# Sheet1.net
KiCad netlist of a schematic drawn in Altium Designer
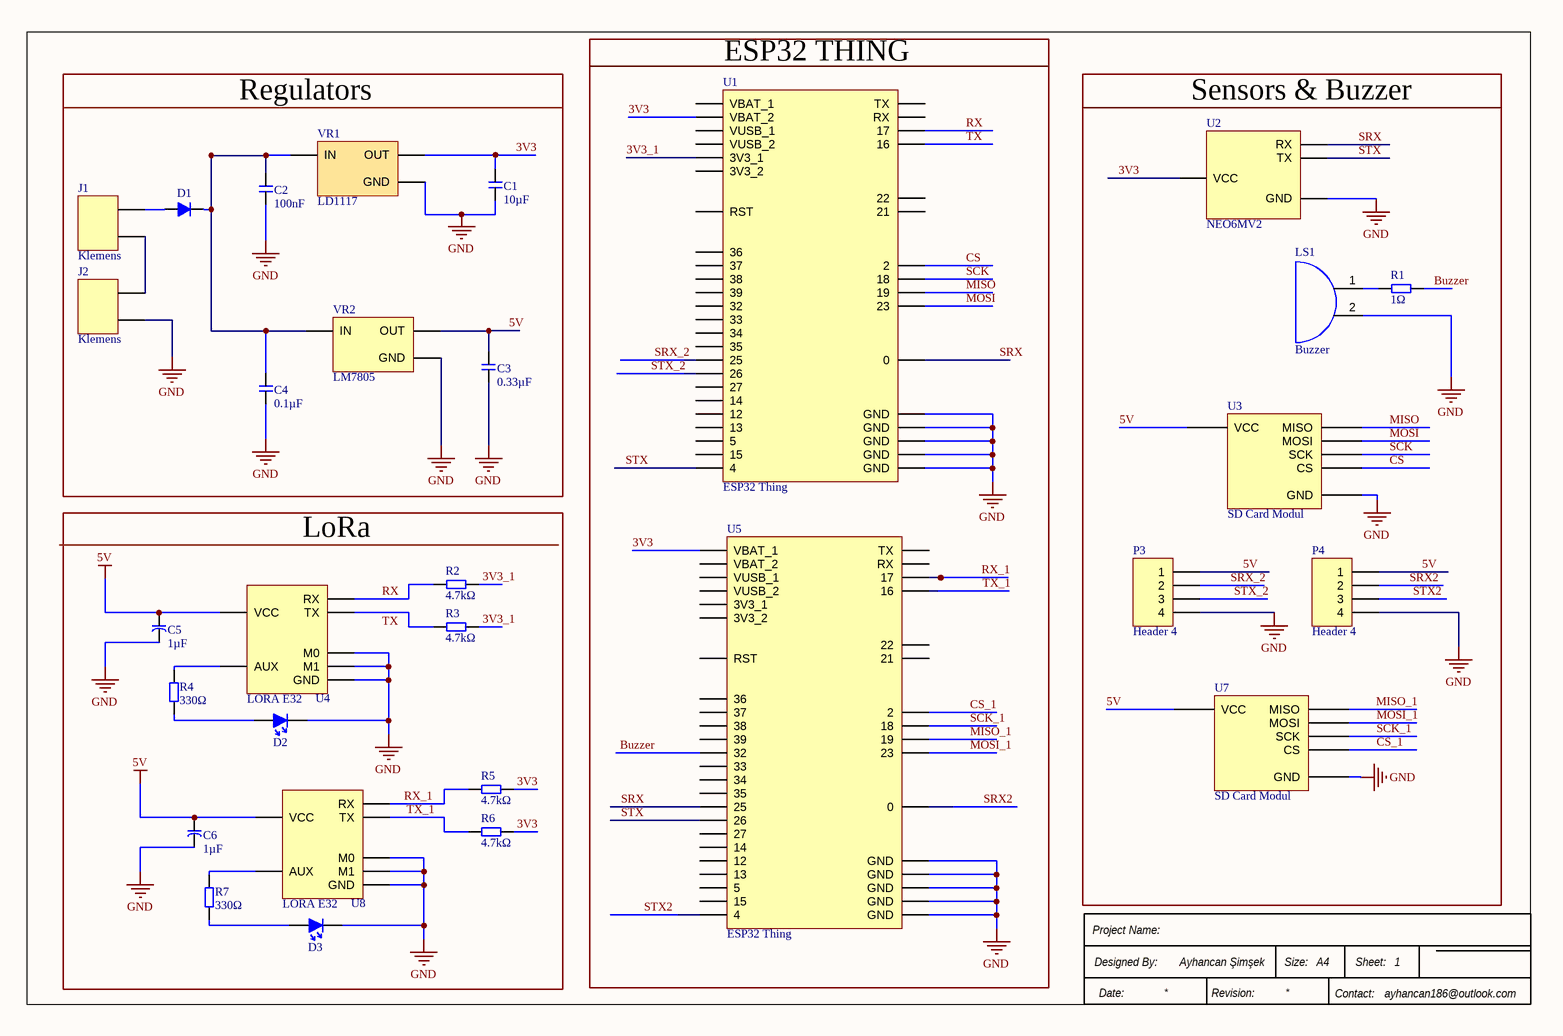
[diagram p0: Sheet1.SchDoc]

(export (version "E")
  (design (tool "Eeschema 10.0.6"))
  (components
    (comp (ref "C1") (value "10µF") (footprint "LCapacitor") (libsource (lib "Schlib1") (part "Capacitor")))
    (comp (ref "C2") (value "100nF") (footprint "LCapacitor") (libsource (lib "Schlib1") (part "Capacitor")))
    (comp (ref "C3") (value "0.33µF") (footprint "LCapacitor") (libsource (lib "Schlib1") (part "Capacitor")))
    (comp (ref "C4") (value "0.1µF") (footprint "LCapacitor") (libsource (lib "Schlib1") (part "Capacitor")))
    (comp (ref "C5") (value "1µF") (footprint "Capacitor") (libsource (lib "Schlib1") (part "DCapacitor")))
    (comp (ref "C6") (value "1µF") (footprint "Capacitor") (libsource (lib "Schlib1") (part "DCapacitor")))
    (comp (ref "D1")
      (value "Diode")
      (footprint "Zener")
      (libsource (lib "Integrated_Library2") (part "Diode"))
    )
    (comp (ref "D2") (value "Led") (footprint "LED") (libsource (lib "Integrated_Library2") (part "Led")))
    (comp (ref "D3") (value "Led") (footprint "LED") (libsource (lib "Integrated_Library2") (part "Led")))
    (comp (ref "J1")
      (value "Klemens")
      (footprint "Klemens")
      (libsource (lib "Integrated_Library2") (part "Klemens"))
    )
    (comp (ref "J2")
      (value "Klemens")
      (footprint "Klemens")
      (libsource (lib "Integrated_Library2") (part "Klemens"))
    )
    (comp (ref "LS1")
      (value "Buzzer")
      (footprint "Buzzer")
      (libsource (lib "Integrated_Library2") (part "Buzzer"))
    )
    (comp (ref "P3")
      (value "Header 4")
      (footprint "HDR1X4")
      (description "Header, 4-Pin")
      (fields (field (name "PUBLISHER") "Altium Limited"))
      (libsource (lib "Miscellaneous Connectors") (part "Header 4"))
    )
    (comp (ref "P4")
      (value "Header 4")
      (footprint "HDR1X4")
      (description "Header, 4-Pin")
      (fields (field (name "PUBLISHER") "Altium Limited"))
      (libsource (lib "Miscellaneous Connectors") (part "Header 4"))
    )
    (comp (ref "R1") (value "1Ω") (footprint "Resistor") (libsource (lib "Schlib1") (part "Resistor")))
    (comp (ref "R2") (value "4.7kΩ") (footprint "Resistor") (libsource (lib "Schlib1") (part "Resistor")))
    (comp (ref "R3") (value "4.7kΩ") (footprint "Resistor") (libsource (lib "Schlib1") (part "Resistor")))
    (comp (ref "R4") (value "330Ω") (footprint "Resistor") (libsource (lib "Schlib1") (part "Resistor")))
    (comp (ref "R5") (value "4.7kΩ") (footprint "Resistor") (libsource (lib "Schlib1") (part "Resistor")))
    (comp (ref "R6") (value "4.7kΩ") (footprint "Resistor") (libsource (lib "Schlib1") (part "Resistor")))
    (comp (ref "R7") (value "330Ω") (footprint "Resistor") (libsource (lib "Schlib1") (part "Resistor")))
    (comp (ref "U1")
      (value "ESP32 Thing")
      (footprint "ESP32 THING")
      (description "ESP32 802.11 Wireless LAN/Combo Wireless Module Development Kit")
      (fields (field (name "MANUFACTURER") "SparkFun") (field (name "MANUFACTURER PART NUMBER") "DEV-13907"))
      (libsource (lib "Integrated_Library2") (part "ESP32 Thing"))
    )
    (comp (ref "U2")
      (value "NEO6MV2")
      (footprint "NEO6MV2")
      (description "U#NEO-6M Gps Module U-BLOX6 SMD24P")
      (fields (field (name "MANUFACTURER") "u-blox") (field (name "MANUFACTURER PART NUMBER") "NEO-6M-0"))
      (libsource (lib "Integrated_Library2") (part "NEO6MV2"))
    )
    (comp (ref "U3")
      (value "SD Card Modul")
      (footprint "SD Card Modülü")
      (libsource (lib "Integrated_Library2") (part "SD Card Modul"))
    )
    (comp (ref "U4")
      (value "LORA E32")
      (footprint "LORAE32")
      (description "WiFi-Modul 802.11/BT 2, 4-2, 5GHz 150Mb/s")
      (fields
        (field (name "MANUFACTURER") "Espressif Systems")
        (field (name "MANUFACTURER PART NUMBER") "ESP32-S3-WROOM-1-N16R8")
      )
      (libsource (lib "Integrated_Library2") (part "LORA E32"))
    )
    (comp (ref "U5")
      (value "ESP32 Thing")
      (footprint "ESP32 THING")
      (description "ESP32 802.11 Wireless LAN/Combo Wireless Module Development Kit")
      (fields (field (name "MANUFACTURER") "SparkFun") (field (name "MANUFACTURER PART NUMBER") "DEV-13907"))
      (libsource (lib "Integrated_Library2") (part "ESP32 Thing"))
    )
    (comp (ref "U7")
      (value "SD Card Modul")
      (footprint "SD Card Modülü")
      (libsource (lib "Integrated_Library2") (part "SD Card Modul"))
    )
    (comp (ref "U8")
      (value "LORA E32")
      (footprint "LORAE32")
      (description "WiFi-Modul 802.11/BT 2, 4-2, 5GHz 150Mb/s")
      (fields
        (field (name "MANUFACTURER") "Espressif Systems")
        (field (name "MANUFACTURER PART NUMBER") "ESP32-S3-WROOM-1-N16R8")
      )
      (libsource (lib "Integrated_Library2") (part "LORA E32"))
    )
    (comp (ref "VR1")
      (value "LD1117")
      (footprint "LD1117")
      (description "LDO Regulator Pos 3.3V 1.3A 3-Pin(3+Tab) TO-220 Tube (Alt: LD1117V33C)")
      (fields
        (field (name "MANUFACTURER") "STMicroelectronics")
        (field (name "MANUFACTURER PART NUMBER") "LD1117V33C")
      )
      (libsource (lib "Integrated_Library2") (part "LD1117"))
    )
    (comp (ref "VR2")
      (value "LM7805")
      (footprint "LM7805")
      (description "LM78XX Series 5 V Fixed Output 1 A 3-Terminal LDO Voltage Regulator - TO-220")
      (fields
        (field (name "MANUFACTURER") "ON Semiconductor / Fairchild")
        (field (name "MANUFACTURER PART NUMBER") "LM7805CT")
      )
      (libsource (lib "Integrated_Library2") (part "LM7805"))
    )
  )
  (nets
    (net (code "1") (name "/3V3") (class "Default")
      (node (ref "C1") (pin "2") (pinfunction "2_2") (pintype "passive"))
      (node (ref "R5") (pin "2") (pinfunction "2_2") (pintype "passive"))
      (node (ref "R6") (pin "2") (pinfunction "2_2") (pintype "passive"))
      (node (ref "U1") (pin "VBAT_2") (pinfunction "VBAT_2_VBAT_2") (pintype "passive"))
      (node (ref "U2") (pin "1") (pinfunction "VCC_1") (pintype "passive"))
      (node (ref "U5") (pin "VBAT_1") (pinfunction "VBAT_1_VBAT_1") (pintype "passive"))
      (node (ref "VR1") (pin "2") (pinfunction "OUT_2") (pintype "passive"))
    )
    (net (code "2") (name "/3V3_1") (class "Default")
      (node (ref "R2") (pin "2") (pinfunction "2_2") (pintype "passive"))
      (node (ref "R3") (pin "2") (pinfunction "2_2") (pintype "passive"))
      (node (ref "U1") (pin "3V3_1") (pinfunction "3V3_1_3V3_1") (pintype "passive"))
    )
    (net (code "3") (name "/Buzzer") (class "Default")
      (node (ref "R1") (pin "1") (pinfunction "1_1") (pintype "passive"))
      (node (ref "U5") (pin "32") (pinfunction "32_32") (pintype "passive"))
    )
    (net (code "4") (name "/CS") (class "Default")
      (node (ref "U1") (pin "2") (pinfunction "2_2") (pintype "passive"))
      (node (ref "U3") (pin "4") (pinfunction "CS_4") (pintype "passive"))
    )
    (net (code "5") (name "/CS_1") (class "Default")
      (node (ref "U5") (pin "2") (pinfunction "2_2") (pintype "passive"))
      (node (ref "U7") (pin "4") (pinfunction "CS_4") (pintype "passive"))
    )
    (net (code "6") (name "/MISO") (class "Default")
      (node (ref "U1") (pin "19") (pinfunction "19_19") (pintype "passive"))
      (node (ref "U3") (pin "3") (pinfunction "MISO_3") (pintype "passive"))
    )
    (net (code "7") (name "/MISO_1") (class "Default")
      (node (ref "U5") (pin "19") (pinfunction "19_19") (pintype "passive"))
      (node (ref "U7") (pin "3") (pinfunction "MISO_3") (pintype "passive"))
    )
    (net (code "8") (name "/MOSI") (class "Default")
      (node (ref "U1") (pin "23") (pinfunction "23_23") (pintype "passive"))
      (node (ref "U3") (pin "2") (pinfunction "MOSI_2") (pintype "passive"))
    )
    (net (code "9") (name "/MOSI_1") (class "Default")
      (node (ref "U5") (pin "23") (pinfunction "23_23") (pintype "passive"))
      (node (ref "U7") (pin "2") (pinfunction "MOSI_2") (pintype "passive"))
    )
    (net (code "10") (name "/RX") (class "Default")
      (node (ref "R2") (pin "1") (pinfunction "1_1") (pintype "passive"))
      (node (ref "U1") (pin "17") (pinfunction "17_17") (pintype "passive"))
      (node (ref "U4") (pin "5") (pinfunction "RX_5") (pintype "passive"))
    )
    (net (code "11") (name "/RX_1") (class "Default")
      (node (ref "R5") (pin "1") (pinfunction "1_1") (pintype "passive"))
      (node (ref "U5") (pin "17") (pinfunction "17_17") (pintype "passive"))
      (node (ref "U8") (pin "5") (pinfunction "RX_5") (pintype "passive"))
    )
    (net (code "12") (name "/SCK") (class "Default")
      (node (ref "U1") (pin "18") (pinfunction "18_18") (pintype "passive"))
      (node (ref "U3") (pin "1") (pinfunction "SCK_1") (pintype "passive"))
    )
    (net (code "13") (name "/SCK_1") (class "Default")
      (node (ref "U5") (pin "18") (pinfunction "18_18") (pintype "passive"))
      (node (ref "U7") (pin "1") (pinfunction "SCK_1") (pintype "passive"))
    )
    (net (code "14") (name "/SRX") (class "Default")
      (node (ref "U1") (pin "0") (pinfunction "0_0") (pintype "passive"))
      (node (ref "U2") (pin "2") (pinfunction "RX_2") (pintype "passive"))
      (node (ref "U5") (pin "25") (pinfunction "25_25") (pintype "passive"))
    )
    (net (code "15") (name "/SRX2") (class "Default")
      (node (ref "P4") (pin "2") (pinfunction "2_2") (pintype "passive"))
      (node (ref "U5") (pin "0") (pinfunction "0_0") (pintype "passive"))
    )
    (net (code "16") (name "/SRX_2") (class "Default")
      (node (ref "P3") (pin "2") (pinfunction "2_2") (pintype "passive"))
      (node (ref "U1") (pin "25") (pinfunction "25_25") (pintype "passive"))
    )
    (net (code "17") (name "/STX") (class "Default")
      (node (ref "U1") (pin "4") (pinfunction "4_4") (pintype "passive"))
      (node (ref "U2") (pin "3") (pinfunction "TX_3") (pintype "passive"))
      (node (ref "U5") (pin "26") (pinfunction "26_26") (pintype "passive"))
    )
    (net (code "18") (name "/STX2") (class "Default")
      (node (ref "P4") (pin "3") (pinfunction "3_3") (pintype "passive"))
      (node (ref "U5") (pin "4") (pinfunction "4_4") (pintype "passive"))
    )
    (net (code "19") (name "/STX_2") (class "Default")
      (node (ref "P3") (pin "3") (pinfunction "3_3") (pintype "passive"))
      (node (ref "U1") (pin "26") (pinfunction "26_26") (pintype "passive"))
    )
    (net (code "20") (name "/TX") (class "Default")
      (node (ref "R3") (pin "1") (pinfunction "1_1") (pintype "passive"))
      (node (ref "U1") (pin "16") (pinfunction "16_16") (pintype "passive"))
      (node (ref "U4") (pin "4") (pinfunction "TX_4") (pintype "passive"))
    )
    (net (code "21") (name "/TX_1") (class "Default")
      (node (ref "R6") (pin "1") (pinfunction "1_1") (pintype "passive"))
      (node (ref "U5") (pin "16") (pinfunction "16_16") (pintype "passive"))
      (node (ref "U8") (pin "4") (pinfunction "TX_4") (pintype "passive"))
    )
    (net (code "22") (name "5V") (class "Default")
      (node (ref "C3") (pin "2") (pinfunction "2_2") (pintype "passive"))
      (node (ref "C5") (pin "1") (pinfunction "1_1") (pintype "passive"))
      (node (ref "C6") (pin "1") (pinfunction "1_1") (pintype "passive"))
      (node (ref "P3") (pin "1") (pinfunction "1_1") (pintype "passive"))
      (node (ref "P4") (pin "1") (pinfunction "1_1") (pintype "passive"))
      (node (ref "U3") (pin "0") (pinfunction "VCC_0") (pintype "passive"))
      (node (ref "U4") (pin "2") (pinfunction "VCC_2") (pintype "passive"))
      (node (ref "U7") (pin "0") (pinfunction "VCC_0") (pintype "passive"))
      (node (ref "U8") (pin "2") (pinfunction "VCC_2") (pintype "passive"))
      (node (ref "VR2") (pin "3") (pinfunction "OUT_3") (pintype "passive"))
    )
    (net (code "23") (name "GND") (class "Default")
      (node (ref "C1") (pin "1") (pinfunction "1_1") (pintype "passive"))
      (node (ref "C2") (pin "1") (pinfunction "1_1") (pintype "passive"))
      (node (ref "C3") (pin "1") (pinfunction "1_1") (pintype "passive"))
      (node (ref "C4") (pin "1") (pinfunction "1_1") (pintype "passive"))
      (node (ref "C5") (pin "2") (pinfunction "2_2") (pintype "passive"))
      (node (ref "C6") (pin "2") (pinfunction "2_2") (pintype "passive"))
      (node (ref "D2") (pin "1") (pinfunction "1_1") (pintype "power_in"))
      (node (ref "D3") (pin "1") (pinfunction "1_1") (pintype "power_in"))
      (node (ref "J2") (pin "1") (pinfunction "1_1") (pintype "passive"))
      (node (ref "LS1") (pin "2") (pinfunction "2_2") (pintype "passive"))
      (node (ref "P3") (pin "4") (pinfunction "4_4") (pintype "passive"))
      (node (ref "P4") (pin "4") (pinfunction "4_4") (pintype "passive"))
      (node (ref "U1") (pin "GND_1") (pinfunction "GND_GND_1") (pintype "passive"))
      (node (ref "U1") (pin "GND_2") (pinfunction "GND_GND_2") (pintype "passive"))
      (node (ref "U1") (pin "GND_3") (pinfunction "GND_GND_3") (pintype "passive"))
      (node (ref "U1") (pin "GND_4") (pinfunction "GND_GND_4") (pintype "passive"))
      (node (ref "U1") (pin "GND_5") (pinfunction "GND_GND_5") (pintype "passive"))
      (node (ref "U2") (pin "4") (pinfunction "GND_4") (pintype "passive"))
      (node (ref "U3") (pin "5") (pinfunction "GND_5") (pintype "passive"))
      (node (ref "U4") (pin "1") (pinfunction "GND_1") (pintype "passive"))
      (node (ref "U4") (pin "6") (pinfunction "M1_6") (pintype "passive"))
      (node (ref "U4") (pin "7") (pinfunction "M0_7") (pintype "passive"))
      (node (ref "U5") (pin "GND_1") (pinfunction "GND_GND_1") (pintype "passive"))
      (node (ref "U5") (pin "GND_2") (pinfunction "GND_GND_2") (pintype "passive"))
      (node (ref "U5") (pin "GND_3") (pinfunction "GND_GND_3") (pintype "passive"))
      (node (ref "U5") (pin "GND_4") (pinfunction "GND_GND_4") (pintype "passive"))
      (node (ref "U5") (pin "GND_5") (pinfunction "GND_GND_5") (pintype "passive"))
      (node (ref "U7") (pin "5") (pinfunction "GND_5") (pintype "passive"))
      (node (ref "U8") (pin "1") (pinfunction "GND_1") (pintype "passive"))
      (node (ref "U8") (pin "6") (pinfunction "M1_6") (pintype "passive"))
      (node (ref "U8") (pin "7") (pinfunction "M0_7") (pintype "passive"))
      (node (ref "VR1") (pin "3") (pinfunction "GND_3") (pintype "passive"))
      (node (ref "VR2") (pin "2") (pinfunction "GND_2") (pintype "passive"))
    )
    (net (code "24") (name "Net-(D1-Pad1)") (class "Default")
      (node (ref "D1") (pin "1") (pinfunction "1_1") (pintype "passive"))
      (node (ref "J1") (pin "0") (pinfunction "0_0") (pintype "passive"))
    )
    (net (code "25") (name "Net-(D2-Pad2)") (class "Default")
      (node (ref "D2") (pin "2") (pinfunction "2_2") (pintype "power_in"))
      (node (ref "R4") (pin "1") (pinfunction "1_1") (pintype "passive"))
    )
    (net (code "26") (name "Net-(D3-Pad2)") (class "Default")
      (node (ref "D3") (pin "2") (pinfunction "2_2") (pintype "power_in"))
      (node (ref "R7") (pin "1") (pinfunction "1_1") (pintype "passive"))
    )
    (net (code "27") (name "Net-(J1-Pad1)") (class "Default")
      (node (ref "J1") (pin "1") (pinfunction "1_1") (pintype "passive"))
      (node (ref "J2") (pin "0") (pinfunction "0_0") (pintype "passive"))
    )
    (net (code "28") (name "Net-(LS1-Pad1)") (class "Default")
      (node (ref "LS1") (pin "1") (pinfunction "1_1") (pintype "passive"))
      (node (ref "R1") (pin "2") (pinfunction "2_2") (pintype "passive"))
    )
    (net (code "29") (name "Net-(U4-AUX)") (class "Default")
      (node (ref "R4") (pin "2") (pinfunction "2_2") (pintype "passive"))
      (node (ref "U4") (pin "3") (pinfunction "AUX_3") (pintype "passive"))
    )
    (net (code "30") (name "Net-(U8-AUX)") (class "Default")
      (node (ref "R7") (pin "2") (pinfunction "2_2") (pintype "passive"))
      (node (ref "U8") (pin "3") (pinfunction "AUX_3") (pintype "passive"))
    )
    (net (code "31") (name "Net-(VR1-IN)") (class "Default")
      (node (ref "C2") (pin "2") (pinfunction "2_2") (pintype "passive"))
      (node (ref "C4") (pin "2") (pinfunction "2_2") (pintype "passive"))
      (node (ref "D1") (pin "2") (pinfunction "2_2") (pintype "passive"))
      (node (ref "VR1") (pin "1") (pinfunction "IN_1") (pintype "passive"))
      (node (ref "VR2") (pin "1") (pinfunction "IN_1") (pintype "passive"))
    )
    (net (code "32") (name "unconnected-(U1-Pad3V3_2)") (class "Default")
      (node (ref "U1") (pin "3V3_2") (pinfunction "3V3_2_3V3_2") (pintype "passive"))
    )
    (net (code "33") (name "unconnected-(U1-Pad5)") (class "Default")
      (node (ref "U1") (pin "5") (pinfunction "5_5") (pintype "passive"))
    )
    (net (code "34") (name "unconnected-(U1-Pad12)") (class "Default")
      (node (ref "U1") (pin "12") (pinfunction "12_12") (pintype "passive"))
    )
    (net (code "35") (name "unconnected-(U1-Pad13)") (class "Default")
      (node (ref "U1") (pin "13") (pinfunction "13_13") (pintype "passive"))
    )
    (net (code "36") (name "unconnected-(U1-Pad14)") (class "Default")
      (node (ref "U1") (pin "14") (pinfunction "14_14") (pintype "passive"))
    )
    (net (code "37") (name "unconnected-(U1-Pad15)") (class "Default")
      (node (ref "U1") (pin "15") (pinfunction "15_15") (pintype "passive"))
    )
    (net (code "38") (name "unconnected-(U1-Pad21)") (class "Default")
      (node (ref "U1") (pin "21") (pinfunction "21_21") (pintype "passive"))
    )
    (net (code "39") (name "unconnected-(U1-Pad22)") (class "Default")
      (node (ref "U1") (pin "22") (pinfunction "22_22") (pintype "passive"))
    )
    (net (code "40") (name "unconnected-(U1-Pad27)") (class "Default")
      (node (ref "U1") (pin "27") (pinfunction "27_27") (pintype "passive"))
    )
    (net (code "41") (name "unconnected-(U1-Pad32)") (class "Default")
      (node (ref "U1") (pin "32") (pinfunction "32_32") (pintype "passive"))
    )
    (net (code "42") (name "unconnected-(U1-Pad33)") (class "Default")
      (node (ref "U1") (pin "33") (pinfunction "33_33") (pintype "passive"))
    )
    (net (code "43") (name "unconnected-(U1-Pad34)") (class "Default")
      (node (ref "U1") (pin "34") (pinfunction "34_34") (pintype "passive"))
    )
    (net (code "44") (name "unconnected-(U1-Pad35)") (class "Default")
      (node (ref "U1") (pin "35") (pinfunction "35_35") (pintype "passive"))
    )
    (net (code "45") (name "unconnected-(U1-Pad36)") (class "Default")
      (node (ref "U1") (pin "36") (pinfunction "36_36") (pintype "passive"))
    )
    (net (code "46") (name "unconnected-(U1-Pad37)") (class "Default")
      (node (ref "U1") (pin "37") (pinfunction "37_37") (pintype "passive"))
    )
    (net (code "47") (name "unconnected-(U1-Pad38)") (class "Default")
      (node (ref "U1") (pin "38") (pinfunction "38_38") (pintype "passive"))
    )
    (net (code "48") (name "unconnected-(U1-Pad39)") (class "Default")
      (node (ref "U1") (pin "39") (pinfunction "39_39") (pintype "passive"))
    )
    (net (code "49") (name "unconnected-(U1-PadRST)") (class "Default")
      (node (ref "U1") (pin "RST") (pinfunction "RST_RST") (pintype "passive"))
    )
    (net (code "50") (name "unconnected-(U1-PadRX)") (class "Default")
      (node (ref "U1") (pin "RX") (pinfunction "RX_RX") (pintype "passive"))
    )
    (net (code "51") (name "unconnected-(U1-PadTX)") (class "Default")
      (node (ref "U1") (pin "TX") (pinfunction "TX_TX") (pintype "passive"))
    )
    (net (code "52") (name "unconnected-(U1-PadVBAT_1)") (class "Default")
      (node (ref "U1") (pin "VBAT_1") (pinfunction "VBAT_1_VBAT_1") (pintype "passive"))
    )
    (net (code "53") (name "unconnected-(U1-PadVUSB_1)") (class "Default")
      (node (ref "U1") (pin "VUSB_1") (pinfunction "VUSB_1_VUSB_1") (pintype "passive"))
    )
    (net (code "54") (name "unconnected-(U1-PadVUSB_2)") (class "Default")
      (node (ref "U1") (pin "VUSB_2") (pinfunction "VUSB_2_VUSB_2") (pintype "passive"))
    )
    (net (code "55") (name "unconnected-(U5-Pad3V3_1)") (class "Default")
      (node (ref "U5") (pin "3V3_1") (pinfunction "3V3_1_3V3_1") (pintype "passive"))
    )
    (net (code "56") (name "unconnected-(U5-Pad3V3_2)") (class "Default")
      (node (ref "U5") (pin "3V3_2") (pinfunction "3V3_2_3V3_2") (pintype "passive"))
    )
    (net (code "57") (name "unconnected-(U5-Pad5)") (class "Default")
      (node (ref "U5") (pin "5") (pinfunction "5_5") (pintype "passive"))
    )
    (net (code "58") (name "unconnected-(U5-Pad12)") (class "Default")
      (node (ref "U5") (pin "12") (pinfunction "12_12") (pintype "passive"))
    )
    (net (code "59") (name "unconnected-(U5-Pad13)") (class "Default")
      (node (ref "U5") (pin "13") (pinfunction "13_13") (pintype "passive"))
    )
    (net (code "60") (name "unconnected-(U5-Pad14)") (class "Default")
      (node (ref "U5") (pin "14") (pinfunction "14_14") (pintype "passive"))
    )
    (net (code "61") (name "unconnected-(U5-Pad15)") (class "Default")
      (node (ref "U5") (pin "15") (pinfunction "15_15") (pintype "passive"))
    )
    (net (code "62") (name "unconnected-(U5-Pad21)") (class "Default")
      (node (ref "U5") (pin "21") (pinfunction "21_21") (pintype "passive"))
    )
    (net (code "63") (name "unconnected-(U5-Pad22)") (class "Default")
      (node (ref "U5") (pin "22") (pinfunction "22_22") (pintype "passive"))
    )
    (net (code "64") (name "unconnected-(U5-Pad27)") (class "Default")
      (node (ref "U5") (pin "27") (pinfunction "27_27") (pintype "passive"))
    )
    (net (code "65") (name "unconnected-(U5-Pad33)") (class "Default")
      (node (ref "U5") (pin "33") (pinfunction "33_33") (pintype "passive"))
    )
    (net (code "66") (name "unconnected-(U5-Pad34)") (class "Default")
      (node (ref "U5") (pin "34") (pinfunction "34_34") (pintype "passive"))
    )
    (net (code "67") (name "unconnected-(U5-Pad35)") (class "Default")
      (node (ref "U5") (pin "35") (pinfunction "35_35") (pintype "passive"))
    )
    (net (code "68") (name "unconnected-(U5-Pad36)") (class "Default")
      (node (ref "U5") (pin "36") (pinfunction "36_36") (pintype "passive"))
    )
    (net (code "69") (name "unconnected-(U5-Pad37)") (class "Default")
      (node (ref "U5") (pin "37") (pinfunction "37_37") (pintype "passive"))
    )
    (net (code "70") (name "unconnected-(U5-Pad38)") (class "Default")
      (node (ref "U5") (pin "38") (pinfunction "38_38") (pintype "passive"))
    )
    (net (code "71") (name "unconnected-(U5-Pad39)") (class "Default")
      (node (ref "U5") (pin "39") (pinfunction "39_39") (pintype "passive"))
    )
    (net (code "72") (name "unconnected-(U5-PadRST)") (class "Default")
      (node (ref "U5") (pin "RST") (pinfunction "RST_RST") (pintype "passive"))
    )
    (net (code "73") (name "unconnected-(U5-PadRX)") (class "Default")
      (node (ref "U5") (pin "RX") (pinfunction "RX_RX") (pintype "passive"))
    )
    (net (code "74") (name "unconnected-(U5-PadTX)") (class "Default")
      (node (ref "U5") (pin "TX") (pinfunction "TX_TX") (pintype "passive"))
    )
    (net (code "75") (name "unconnected-(U5-PadVBAT_2)") (class "Default")
      (node (ref "U5") (pin "VBAT_2") (pinfunction "VBAT_2_VBAT_2") (pintype "passive"))
    )
    (net (code "76") (name "unconnected-(U5-PadVUSB_1)") (class "Default")
      (node (ref "U5") (pin "VUSB_1") (pinfunction "VUSB_1_VUSB_1") (pintype "passive"))
    )
    (net (code "77") (name "unconnected-(U5-PadVUSB_2)") (class "Default")
      (node (ref "U5") (pin "VUSB_2") (pinfunction "VUSB_2_VUSB_2") (pintype "passive"))
    )
  )
)
